# alim_1.net
KiCad netlist of a schematic drawn in EAGLE
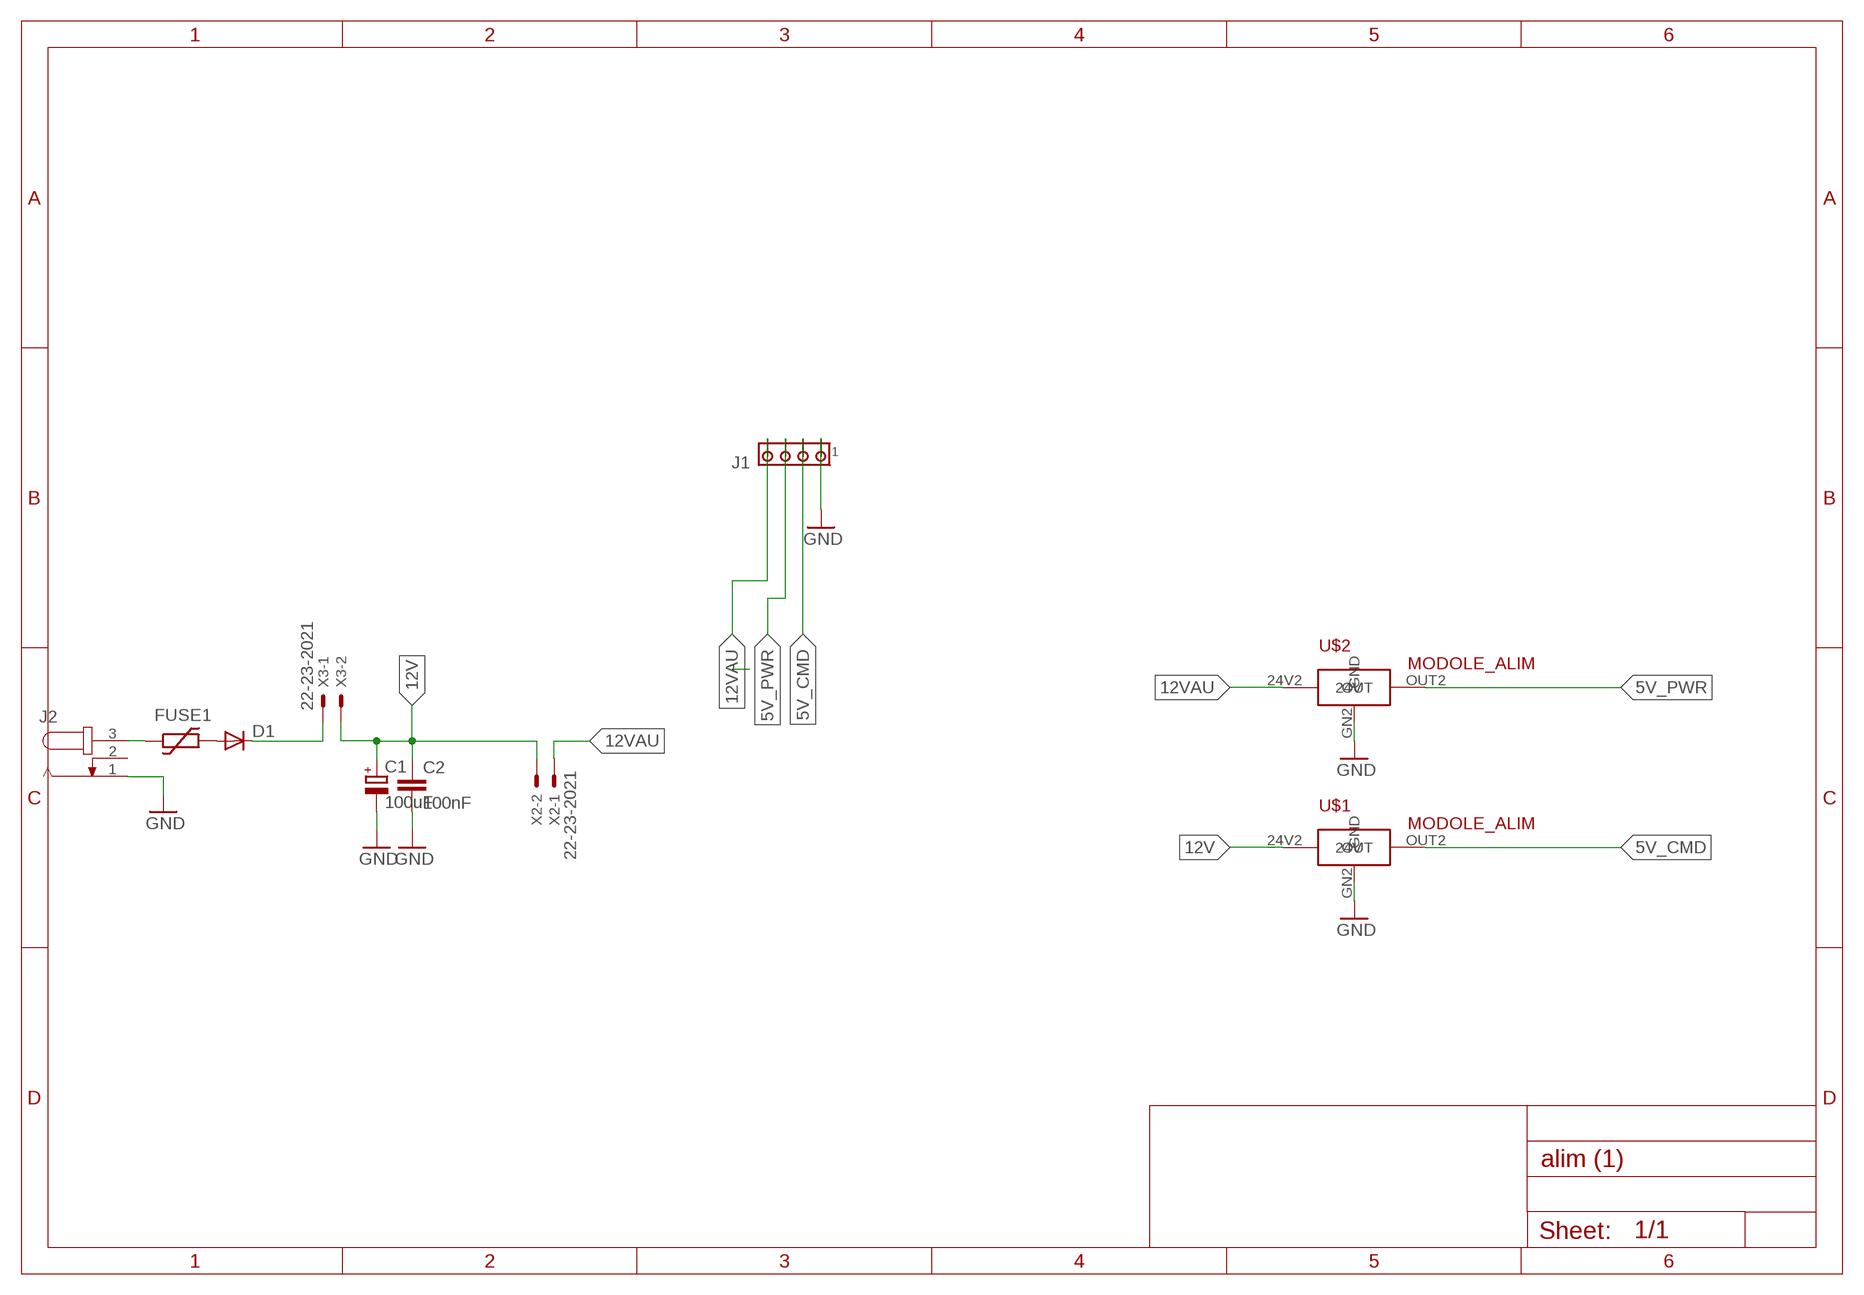
[diagram p0: schematic, sheet 1]

(export (version "E")
  (design (tool "Eeschema 10.0.6"))
  (components
    (comp (ref "C1")
      (value "100uF")
      (footprint "eagle-import:E2,5-7")
      (libsource (lib "eagle-import") (part "CPOL-EUE2.5-7"))
    )
    (comp (ref "C2")
      (value "100nF")
      (footprint "eagle-import:C050-035X075")
      (libsource (lib "eagle-import") (part "C-EU050-035X075"))
    )
    (comp (ref "D1")
      (value "DIODE-DO07")
      (footprint "eagle-import:DO07")
      (libsource (lib "eagle-import") (part "DIODE-DO07"))
    )
    (comp (ref "FUSE1")
      (value "MINI_SMD_C")
      (footprint "eagle-import:MINI_SMD_C")
      (libsource (lib "eagle-import") (part "MINI_SMD_C"))
    )
    (comp (ref "J1")
      (value "MTA04-100")
      (footprint "eagle-import:10X04MTA")
      (libsource (lib "eagle-import") (part "MTA04-100"))
    )
    (comp (ref "J2")
      (value "JACK-PLUG1")
      (footprint "eagle-import:SPC4078")
      (libsource (lib "eagle-import") (part "JACK-PLUG1"))
    )
    (comp (ref "U$1")
      (value "MODOLE_ALIM")
      (footprint "eagle-import:PETITE_ALIM")
      (libsource (lib "eagle-import") (part "MODOLE_ALIM"))
    )
    (comp (ref "U$2")
      (value "MODOLE_ALIM")
      (footprint "eagle-import:PETITE_ALIM")
      (libsource (lib "eagle-import") (part "MODOLE_ALIM"))
    )
    (comp (ref "X2")
      (value "22-23-2021")
      (footprint "eagle-import:22-23-2021")
      (fields (field (name "MF") "MOLEX"))
      (libsource (lib "eagle-import") (part "22-23-2021"))
    )
    (comp (ref "X3")
      (value "22-23-2021")
      (footprint "eagle-import:22-23-2021")
      (fields (field (name "MF") "MOLEX"))
      (libsource (lib "eagle-import") (part "22-23-2021"))
    )
  )
  (nets
    (net (code "1") (name "5V_CMD") (class "Default")
      (node (ref "J1") (pin "2") (pinfunction "2_2") (pintype "passive"))
      (node (ref "U$1") (pin "OUT2") (pinfunction "OUT_OUT2") (pintype "bidirectional"))
    )
    (net (code "2") (name "5V_PWR") (class "Default")
      (node (ref "J1") (pin "3") (pinfunction "3_3") (pintype "passive"))
      (node (ref "U$2") (pin "OUT2") (pinfunction "OUT_OUT2") (pintype "bidirectional"))
    )
    (net (code "3") (name "12V") (class "Default")
      (node (ref "C1") (pin "+") (pinfunction "+_+") (pintype "passive"))
      (node (ref "C2") (pin "1") (pinfunction "1_1") (pintype "passive"))
      (node (ref "U$1") (pin "24V2") (pinfunction "24V_24V2") (pintype "bidirectional"))
      (node (ref "X2") (pin "2") (pinfunction "S_2") (pintype "passive"))
      (node (ref "X3") (pin "2") (pinfunction "S_2") (pintype "passive"))
    )
    (net (code "4") (name "12VAU") (class "Default")
      (node (ref "J1") (pin "4") (pinfunction "4_4") (pintype "passive"))
      (node (ref "U$2") (pin "24V2") (pinfunction "24V_24V2") (pintype "bidirectional"))
      (node (ref "X2") (pin "1") (pinfunction "S_1") (pintype "passive"))
    )
    (net (code "5") (name "GND") (class "Default")
      (node (ref "C1") (pin "-") (pinfunction "-_-") (pintype "passive"))
      (node (ref "C2") (pin "2") (pinfunction "2_2") (pintype "passive"))
      (node (ref "J1") (pin "1") (pinfunction "1_1") (pintype "passive"))
      (node (ref "J2") (pin "1") (pinfunction "1_1") (pintype "passive"))
      (node (ref "U$1") (pin "GN2") (pinfunction "GND_GN2") (pintype "bidirectional"))
      (node (ref "U$2") (pin "GN2") (pinfunction "GND_GN2") (pintype "bidirectional"))
    )
    (net (code "6") (name "Net-(FUSE1-1)") (class "Default")
      (node (ref "FUSE1") (pin "P$1") (pinfunction "1_P$1") (pintype "passive"))
      (node (ref "J2") (pin "3") (pinfunction "3_3") (pintype "passive"))
    )
    (net (code "7") (name "Net-(FUSE1-2)") (class "Default")
      (node (ref "D1") (pin "A") (pinfunction "A_A") (pintype "passive"))
      (node (ref "FUSE1") (pin "P$2") (pinfunction "2_P$2") (pintype "passive"))
    )
    (net (code "8") (name "Net-(X3A-S)") (class "Default")
      (node (ref "D1") (pin "C") (pinfunction "C_C") (pintype "passive"))
      (node (ref "X3") (pin "1") (pinfunction "S_1") (pintype "passive"))
    )
    (net (code "9") (name "unconnected-(J2-Pad2)") (class "Default")
      (node (ref "J2") (pin "2") (pinfunction "2_2") (pintype "passive"))
    )
  )
)
